# BU01.net
KiCad netlist of a schematic drawn in Altium Designer
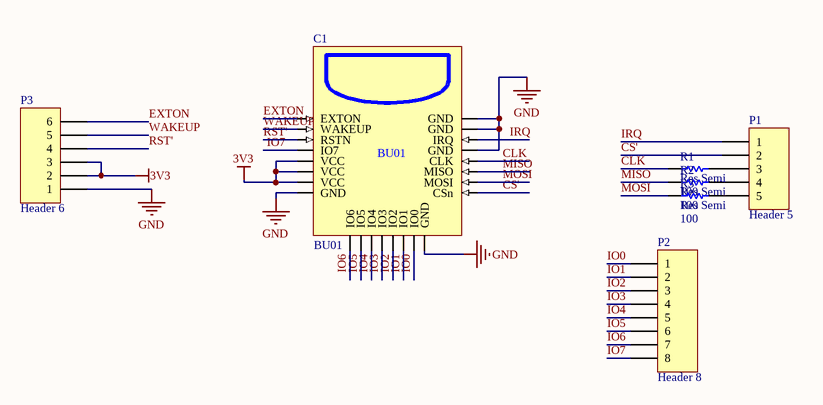
[diagram p0: BU01.SchDoc]

(export (version "E")
  (design (tool "Eeschema 10.0.6"))
  (components
    (comp (ref "C1") (value "BU01") (footprint "BU01") (libsource (lib "BU01") (part "BU01")))
    (comp (ref "P1")
      (value "Header 5")
      (footprint "HDR1X5")
      (description "Header, 5-Pin")
      (fields (field (name "PUBLISHER") "Altium Limited"))
      (libsource (lib "Miscellaneous Connectors") (part "Header 5"))
    )
    (comp (ref "P2")
      (value "Header 8")
      (footprint "HDR1X8")
      (description "Header, 8-Pin")
      (fields (field (name "PUBLISHER") "Altium Limited"))
      (libsource (lib "Miscellaneous Connectors") (part "Header 8"))
    )
    (comp (ref "P3")
      (value "Header 6")
      (footprint "HDR1X6")
      (description "Header, 6-Pin")
      (fields (field (name "PUBLISHER") "Altium Limited"))
      (libsource (lib "Miscellaneous Connectors") (part "Header 6"))
    )
    (comp (ref "R1")
      (value "Res Semi")
      (footprint "0805")
      (description "Semiconductor Resistor")
      (fields (field (name "ALTIUM_VALUE") "100") (field (name "PUBLISHER") "Altium Limited"))
      (libsource (lib "Miscellaneous Devices") (part "Res Semi"))
    )
    (comp (ref "R2")
      (value "Res Semi")
      (footprint "0805")
      (description "Semiconductor Resistor")
      (fields (field (name "ALTIUM_VALUE") "100") (field (name "PUBLISHER") "Altium Limited"))
      (libsource (lib "Miscellaneous Devices") (part "Res Semi"))
    )
    (comp (ref "R3")
      (value "Res Semi")
      (footprint "0805")
      (description "Semiconductor Resistor")
      (fields (field (name "ALTIUM_VALUE") "100") (field (name "PUBLISHER") "Altium Limited"))
      (libsource (lib "Miscellaneous Devices") (part "Res Semi"))
    )
  )
  (nets
    (net (code "1") (name "/CLK") (class "Default")
      (node (ref "C1") (pin "20") (pinfunction "CLK_20") (pintype "input"))
      (node (ref "R1") (pin "1") (pinfunction "1_1") (pintype "passive"))
    )
    (net (code "2") (name "/CS'") (class "Default")
      (node (ref "C1") (pin "17") (pinfunction "CSn_17") (pintype "input"))
      (node (ref "P1") (pin "2") (pinfunction "2_2") (pintype "passive"))
    )
    (net (code "3") (name "/EXTON") (class "Default")
      (node (ref "C1") (pin "1") (pinfunction "EXTON_1") (pintype "input"))
      (node (ref "P3") (pin "6") (pinfunction "6_6") (pintype "passive"))
    )
    (net (code "4") (name "/IO0") (class "Default")
      (node (ref "C1") (pin "15") (pinfunction "IO0_15") (pintype "bidirectional"))
      (node (ref "P2") (pin "1") (pinfunction "1_1") (pintype "passive"))
    )
    (net (code "5") (name "/IO1") (class "Default")
      (node (ref "C1") (pin "14") (pinfunction "IO1_14") (pintype "bidirectional"))
      (node (ref "P2") (pin "2") (pinfunction "2_2") (pintype "passive"))
    )
    (net (code "6") (name "/IO2") (class "Default")
      (node (ref "C1") (pin "13") (pinfunction "IO2_13") (pintype "bidirectional"))
      (node (ref "P2") (pin "3") (pinfunction "3_3") (pintype "passive"))
    )
    (net (code "7") (name "/IO3") (class "Default")
      (node (ref "C1") (pin "12") (pinfunction "IO3_12") (pintype "bidirectional"))
      (node (ref "P2") (pin "4") (pinfunction "4_4") (pintype "passive"))
    )
    (net (code "8") (name "/IO4") (class "Default")
      (node (ref "C1") (pin "11") (pinfunction "IO4_11") (pintype "bidirectional"))
      (node (ref "P2") (pin "5") (pinfunction "5_5") (pintype "passive"))
    )
    (net (code "9") (name "/IO5") (class "Default")
      (node (ref "C1") (pin "10") (pinfunction "IO5_10") (pintype "bidirectional"))
      (node (ref "P2") (pin "6") (pinfunction "6_6") (pintype "passive"))
    )
    (net (code "10") (name "/IO6") (class "Default")
      (node (ref "C1") (pin "9") (pinfunction "IO6_9") (pintype "bidirectional"))
      (node (ref "P2") (pin "7") (pinfunction "7_7") (pintype "passive"))
    )
    (net (code "11") (name "/IO7") (class "Default")
      (node (ref "C1") (pin "4") (pinfunction "IO7_4") (pintype "bidirectional"))
      (node (ref "P2") (pin "8") (pinfunction "8_8") (pintype "passive"))
    )
    (net (code "12") (name "/IRQ") (class "Default")
      (node (ref "C1") (pin "22") (pinfunction "IRQ_22") (pintype "input"))
      (node (ref "P1") (pin "1") (pinfunction "1_1") (pintype "passive"))
    )
    (net (code "13") (name "/MISO") (class "Default")
      (node (ref "C1") (pin "19") (pinfunction "MISO_19") (pintype "input"))
      (node (ref "R2") (pin "1") (pinfunction "1_1") (pintype "passive"))
    )
    (net (code "14") (name "/MOSI") (class "Default")
      (node (ref "C1") (pin "18") (pinfunction "MOSI_18") (pintype "input"))
      (node (ref "R3") (pin "1") (pinfunction "1_1") (pintype "passive"))
    )
    (net (code "15") (name "/RST'") (class "Default")
      (node (ref "C1") (pin "3") (pinfunction "RSTN_3") (pintype "input"))
      (node (ref "P3") (pin "4") (pinfunction "4_4") (pintype "passive"))
    )
    (net (code "16") (name "/WAKEUP") (class "Default")
      (node (ref "C1") (pin "2") (pinfunction "WAKEUP_2") (pintype "input"))
      (node (ref "P3") (pin "5") (pinfunction "5_5") (pintype "passive"))
    )
    (net (code "17") (name "3V3") (class "Default")
      (node (ref "C1") (pin "5") (pinfunction "VCC_5") (pintype "power_in"))
      (node (ref "C1") (pin "6") (pinfunction "VCC_6") (pintype "power_in"))
      (node (ref "C1") (pin "7") (pinfunction "VCC_7") (pintype "power_in"))
      (node (ref "P3") (pin "2") (pinfunction "2_2") (pintype "passive"))
      (node (ref "P3") (pin "3") (pinfunction "3_3") (pintype "passive"))
    )
    (net (code "18") (name "GND") (class "Default")
      (node (ref "C1") (pin "16") (pinfunction "GND_16") (pintype "power_in"))
      (node (ref "C1") (pin "21") (pinfunction "GND_21") (pintype "passive"))
      (node (ref "C1") (pin "23") (pinfunction "GND_23") (pintype "passive"))
      (node (ref "C1") (pin "24") (pinfunction "GND_24") (pintype "passive"))
      (node (ref "C1") (pin "8") (pinfunction "GND_8") (pintype "power_in"))
      (node (ref "P3") (pin "1") (pinfunction "1_1") (pintype "passive"))
    )
    (net (code "19") (name "Net-(P1-Pad3)") (class "Default")
      (node (ref "P1") (pin "3") (pinfunction "3_3") (pintype "passive"))
      (node (ref "R1") (pin "2") (pinfunction "2_2") (pintype "passive"))
    )
    (net (code "20") (name "Net-(P1-Pad4)") (class "Default")
      (node (ref "P1") (pin "4") (pinfunction "4_4") (pintype "passive"))
      (node (ref "R2") (pin "2") (pinfunction "2_2") (pintype "passive"))
    )
    (net (code "21") (name "Net-(P1-Pad5)") (class "Default")
      (node (ref "P1") (pin "5") (pinfunction "5_5") (pintype "passive"))
      (node (ref "R3") (pin "2") (pinfunction "2_2") (pintype "passive"))
    )
  )
)
